# Sheet2.net
KiCad netlist of a schematic drawn in Altium Designer
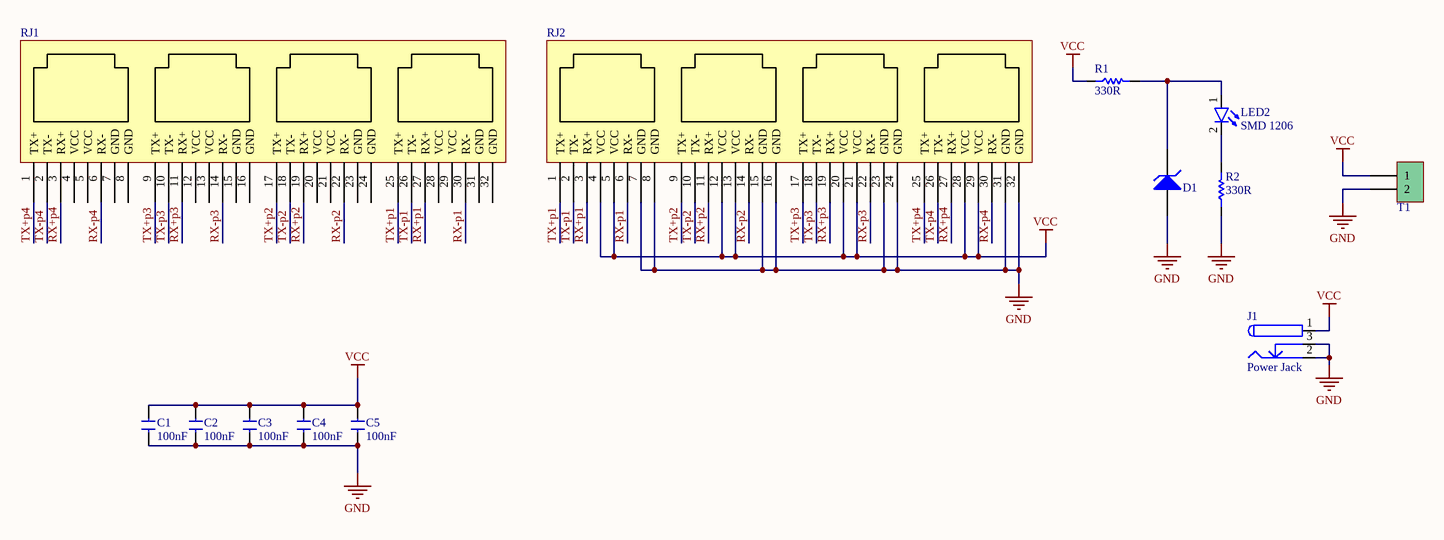
[diagram p0: Sheet2.SchDoc]

(export (version "E")
  (design (tool "Eeschema 10.0.6"))
  (components
    (comp (ref "C1")
      (value "Capacitor SMD")
      (footprint "1206 Capacitor")
      (fields (field (name "ALTIUM_UNNAMED_1") "100nF"))
      (libsource (lib "ZetaBoard_Lib") (part "Capacitor SMD"))
    )
    (comp (ref "C2")
      (value "Capacitor SMD")
      (footprint "1206 Capacitor")
      (fields (field (name "ALTIUM_UNNAMED_1") "100nF"))
      (libsource (lib "ZetaBoard_Lib") (part "Capacitor SMD"))
    )
    (comp (ref "C3")
      (value "Capacitor SMD")
      (footprint "1206 Capacitor")
      (fields (field (name "ALTIUM_UNNAMED_1") "100nF"))
      (libsource (lib "ZetaBoard_Lib") (part "Capacitor SMD"))
    )
    (comp (ref "C4")
      (value "Capacitor SMD")
      (footprint "1206 Capacitor")
      (fields (field (name "ALTIUM_UNNAMED_1") "100nF"))
      (libsource (lib "ZetaBoard_Lib") (part "Capacitor SMD"))
    )
    (comp (ref "C5")
      (value "Capacitor SMD")
      (footprint "1206 Capacitor")
      (fields (field (name "ALTIUM_UNNAMED_1") "100nF"))
      (libsource (lib "ZetaBoard_Lib") (part "Capacitor SMD"))
    )
    (comp (ref "D1")
      (value "Diode Zener")
      (footprint "Diode 1W")
      (description "Zener Diode")
      (fields (field (name "VOLTAGE") "12V") (field (name "DESIGNER") "Saeid Jorablo"))
      (libsource (lib "Electrovolt Lib") (part "Diode Zener"))
    )
    (comp (ref "J1")
      (value "Power Jack")
      (footprint "Power Jack")
      (fields (field (name "DESIGNER") "Saeid Jorablo"))
      (libsource (lib "Electrovolt Lib") (part "Power Jack"))
    )
    (comp (ref "LED2")
      (value "Red")
      (footprint "LED-5mm")
      (description "LED")
      (fields (field (name "SIZE") "SMD 1206") (field (name "DESIGNER") "Saeid Jorablo"))
      (libsource (lib "Electrovolt Lib") (part "LED"))
    )
    (comp (ref "R1")
      (value "330R")
      (footprint "Res-(1/2)")
      (description "Resistor")
      (fields (field (name "TOLERANCE") "5%") (field (name "POWER") "1/8 W"))
      (libsource (lib "Electrovolt Lib") (part "Resistor"))
    )
    (comp (ref "R2")
      (value "330R")
      (footprint "RES 1206 (3216X08L)")
      (description "Resistor")
      (fields (field (name "TOLERANCE") "5%") (field (name "POWER") "1/8 W"))
      (libsource (lib "Electrovolt Lib") (part "Resistor"))
    )
    (comp (ref "RJ1") (value "~") (footprint "rj45-w57-4") (libsource (lib "Schlib1") (part "RJ45-w57-4")))
    (comp (ref "RJ2") (value "~") (footprint "rj45-w57-4") (libsource (lib "Schlib1") (part "RJ45-w57-4")))
    (comp (ref "T1")
      (value "Phoenix terminal")
      (footprint "phoenix terminal 2")
      (description "Terminal 2 Pin")
      (fields (field (name "DESIGNER") "Seyed Mohsen Ghasemain") (field (name "E-MAIL") "picpars@gmail.com"))
      (libsource (lib "usefully_Library") (part "Phoenix terminal 2"))
    )
  )
  (nets
    (net (code "1") (name "/RX+p1") (class "Default")
      (node (ref "RJ1") (pin "27") (pinfunction "RX+_27") (pintype "passive"))
      (node (ref "RJ2") (pin "3") (pinfunction "RX+_3") (pintype "passive"))
    )
    (net (code "2") (name "/RX+p2") (class "Default")
      (node (ref "RJ1") (pin "19") (pinfunction "RX+_19") (pintype "passive"))
      (node (ref "RJ2") (pin "11") (pinfunction "RX+_11") (pintype "passive"))
    )
    (net (code "3") (name "/RX+p3") (class "Default")
      (node (ref "RJ1") (pin "11") (pinfunction "RX+_11") (pintype "passive"))
      (node (ref "RJ2") (pin "19") (pinfunction "RX+_19") (pintype "passive"))
    )
    (net (code "4") (name "/RX+p4") (class "Default")
      (node (ref "RJ1") (pin "3") (pinfunction "RX+_3") (pintype "passive"))
      (node (ref "RJ2") (pin "27") (pinfunction "RX+_27") (pintype "passive"))
    )
    (net (code "5") (name "/RX-p1") (class "Default")
      (node (ref "RJ1") (pin "30") (pinfunction "RX-_30") (pintype "passive"))
      (node (ref "RJ2") (pin "6") (pinfunction "RX-_6") (pintype "passive"))
    )
    (net (code "6") (name "/RX-p2") (class "Default")
      (node (ref "RJ1") (pin "22") (pinfunction "RX-_22") (pintype "passive"))
      (node (ref "RJ2") (pin "14") (pinfunction "RX-_14") (pintype "passive"))
    )
    (net (code "7") (name "/RX-p3") (class "Default")
      (node (ref "RJ1") (pin "14") (pinfunction "RX-_14") (pintype "passive"))
      (node (ref "RJ2") (pin "22") (pinfunction "RX-_22") (pintype "passive"))
    )
    (net (code "8") (name "/RX-p4") (class "Default")
      (node (ref "RJ1") (pin "6") (pinfunction "RX-_6") (pintype "passive"))
      (node (ref "RJ2") (pin "30") (pinfunction "RX-_30") (pintype "passive"))
    )
    (net (code "9") (name "/TX+p1") (class "Default")
      (node (ref "RJ1") (pin "25") (pinfunction "TX+_25") (pintype "passive"))
      (node (ref "RJ2") (pin "1") (pinfunction "TX+_1") (pintype "passive"))
    )
    (net (code "10") (name "/TX+p2") (class "Default")
      (node (ref "RJ1") (pin "17") (pinfunction "TX+_17") (pintype "passive"))
      (node (ref "RJ2") (pin "9") (pinfunction "TX+_9") (pintype "passive"))
    )
    (net (code "11") (name "/TX+p3") (class "Default")
      (node (ref "RJ1") (pin "9") (pinfunction "TX+_9") (pintype "passive"))
      (node (ref "RJ2") (pin "17") (pinfunction "TX+_17") (pintype "passive"))
    )
    (net (code "12") (name "/TX+p4") (class "Default")
      (node (ref "RJ1") (pin "1") (pinfunction "TX+_1") (pintype "passive"))
      (node (ref "RJ2") (pin "25") (pinfunction "TX+_25") (pintype "passive"))
    )
    (net (code "13") (name "/TX-p1") (class "Default")
      (node (ref "RJ1") (pin "26") (pinfunction "TX-_26") (pintype "passive"))
      (node (ref "RJ2") (pin "2") (pinfunction "TX-_2") (pintype "passive"))
    )
    (net (code "14") (name "/TX-p2") (class "Default")
      (node (ref "RJ1") (pin "18") (pinfunction "TX-_18") (pintype "passive"))
      (node (ref "RJ2") (pin "10") (pinfunction "TX-_10") (pintype "passive"))
    )
    (net (code "15") (name "/TX-p3") (class "Default")
      (node (ref "RJ1") (pin "10") (pinfunction "TX-_10") (pintype "passive"))
      (node (ref "RJ2") (pin "18") (pinfunction "TX-_18") (pintype "passive"))
    )
    (net (code "16") (name "/TX-p4") (class "Default")
      (node (ref "RJ1") (pin "2") (pinfunction "TX-_2") (pintype "passive"))
      (node (ref "RJ2") (pin "26") (pinfunction "TX-_26") (pintype "passive"))
    )
    (net (code "17") (name "GND") (class "Default")
      (node (ref "C1") (pin "1") (pintype "passive"))
      (node (ref "C2") (pin "1") (pintype "passive"))
      (node (ref "C3") (pin "1") (pintype "passive"))
      (node (ref "C4") (pin "1") (pintype "passive"))
      (node (ref "C5") (pin "1") (pintype "passive"))
      (node (ref "D1") (pin "1") (pinfunction "A_1") (pintype "passive"))
      (node (ref "J1") (pin "2") (pinfunction "2_2") (pintype "power_in"))
      (node (ref "J1") (pin "3") (pinfunction "3_3") (pintype "power_in"))
      (node (ref "R2") (pin "1") (pinfunction "1_1") (pintype "passive"))
      (node (ref "RJ2") (pin "15") (pinfunction "GND_15") (pintype "passive"))
      (node (ref "RJ2") (pin "16") (pinfunction "GND_16") (pintype "passive"))
      (node (ref "RJ2") (pin "23") (pinfunction "GND_23") (pintype "passive"))
      (node (ref "RJ2") (pin "24") (pinfunction "GND_24") (pintype "passive"))
      (node (ref "RJ2") (pin "31") (pinfunction "GND_31") (pintype "passive"))
      (node (ref "RJ2") (pin "32") (pinfunction "GND_32") (pintype "passive"))
      (node (ref "RJ2") (pin "7") (pinfunction "GND_7") (pintype "passive"))
      (node (ref "RJ2") (pin "8") (pinfunction "GND_8") (pintype "passive"))
      (node (ref "T1") (pin "2") (pinfunction "2_2") (pintype "passive"))
    )
    (net (code "18") (name "Net-(D1-K)") (class "Default")
      (node (ref "D1") (pin "2") (pinfunction "K_2") (pintype "passive"))
      (node (ref "LED2") (pin "1") (pinfunction "A_1") (pintype "passive"))
      (node (ref "R1") (pin "2") (pinfunction "2_2") (pintype "passive"))
    )
    (net (code "19") (name "Net-(LED2-K)") (class "Default")
      (node (ref "LED2") (pin "2") (pinfunction "K_2") (pintype "passive"))
      (node (ref "R2") (pin "2") (pinfunction "2_2") (pintype "passive"))
    )
    (net (code "20") (name "VCC") (class "Default")
      (node (ref "C1") (pin "2") (pintype "passive"))
      (node (ref "C2") (pin "2") (pintype "passive"))
      (node (ref "C3") (pin "2") (pintype "passive"))
      (node (ref "C4") (pin "2") (pintype "passive"))
      (node (ref "C5") (pin "2") (pintype "passive"))
      (node (ref "J1") (pin "1") (pinfunction "1_1") (pintype "power_in"))
      (node (ref "R1") (pin "1") (pinfunction "1_1") (pintype "passive"))
      (node (ref "RJ2") (pin "12") (pinfunction "VCC_12") (pintype "passive"))
      (node (ref "RJ2") (pin "13") (pinfunction "VCC_13") (pintype "passive"))
      (node (ref "RJ2") (pin "20") (pinfunction "VCC_20") (pintype "passive"))
      (node (ref "RJ2") (pin "21") (pinfunction "VCC_21") (pintype "passive"))
      (node (ref "RJ2") (pin "28") (pinfunction "VCC_28") (pintype "passive"))
      (node (ref "RJ2") (pin "29") (pinfunction "VCC_29") (pintype "passive"))
      (node (ref "RJ2") (pin "4") (pinfunction "VCC_4") (pintype "passive"))
      (node (ref "RJ2") (pin "5") (pinfunction "VCC_5") (pintype "passive"))
      (node (ref "T1") (pin "1") (pinfunction "1_1") (pintype "passive"))
    )
    (net (code "21") (name "unconnected-(RJ1-GND-Pad7)") (class "Default")
      (node (ref "RJ1") (pin "7") (pinfunction "GND_7") (pintype "passive"))
    )
    (net (code "22") (name "unconnected-(RJ1-GND-Pad8)") (class "Default")
      (node (ref "RJ1") (pin "8") (pinfunction "GND_8") (pintype "passive"))
    )
    (net (code "23") (name "unconnected-(RJ1-GND-Pad15)") (class "Default")
      (node (ref "RJ1") (pin "15") (pinfunction "GND_15") (pintype "passive"))
    )
    (net (code "24") (name "unconnected-(RJ1-GND-Pad16)") (class "Default")
      (node (ref "RJ1") (pin "16") (pinfunction "GND_16") (pintype "passive"))
    )
    (net (code "25") (name "unconnected-(RJ1-GND-Pad23)") (class "Default")
      (node (ref "RJ1") (pin "23") (pinfunction "GND_23") (pintype "passive"))
    )
    (net (code "26") (name "unconnected-(RJ1-GND-Pad24)") (class "Default")
      (node (ref "RJ1") (pin "24") (pinfunction "GND_24") (pintype "passive"))
    )
    (net (code "27") (name "unconnected-(RJ1-GND-Pad31)") (class "Default")
      (node (ref "RJ1") (pin "31") (pinfunction "GND_31") (pintype "passive"))
    )
    (net (code "28") (name "unconnected-(RJ1-GND-Pad32)") (class "Default")
      (node (ref "RJ1") (pin "32") (pinfunction "GND_32") (pintype "passive"))
    )
    (net (code "29") (name "unconnected-(RJ1-VCC-Pad4)") (class "Default")
      (node (ref "RJ1") (pin "4") (pinfunction "VCC_4") (pintype "passive"))
    )
    (net (code "30") (name "unconnected-(RJ1-VCC-Pad5)") (class "Default")
      (node (ref "RJ1") (pin "5") (pinfunction "VCC_5") (pintype "passive"))
    )
    (net (code "31") (name "unconnected-(RJ1-VCC-Pad12)") (class "Default")
      (node (ref "RJ1") (pin "12") (pinfunction "VCC_12") (pintype "passive"))
    )
    (net (code "32") (name "unconnected-(RJ1-VCC-Pad13)") (class "Default")
      (node (ref "RJ1") (pin "13") (pinfunction "VCC_13") (pintype "passive"))
    )
    (net (code "33") (name "unconnected-(RJ1-VCC-Pad20)") (class "Default")
      (node (ref "RJ1") (pin "20") (pinfunction "VCC_20") (pintype "passive"))
    )
    (net (code "34") (name "unconnected-(RJ1-VCC-Pad21)") (class "Default")
      (node (ref "RJ1") (pin "21") (pinfunction "VCC_21") (pintype "passive"))
    )
    (net (code "35") (name "unconnected-(RJ1-VCC-Pad28)") (class "Default")
      (node (ref "RJ1") (pin "28") (pinfunction "VCC_28") (pintype "passive"))
    )
    (net (code "36") (name "unconnected-(RJ1-VCC-Pad29)") (class "Default")
      (node (ref "RJ1") (pin "29") (pinfunction "VCC_29") (pintype "passive"))
    )
  )
)
